# 230V2LED.net
KiCad netlist of a schematic drawn in EAGLE
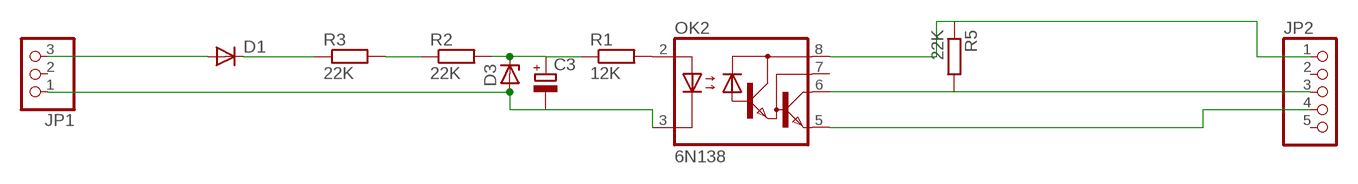
[diagram p0: schematic, sheet 1]

(export (version "E")
  (design (tool "Eeschema 10.0.6"))
  (components
    (comp (ref "C3")
      (value "CPOL-EUE2,5-6E")
      (footprint "eagle-import:E2,5-6E")
      (libsource (lib "eagle-import") (part "CPOL-EUE2,5-6E"))
    )
    (comp (ref "D1")
      (value "DIODE-D-2.5")
      (footprint "eagle-import:D-2.5")
      (libsource (lib "eagle-import") (part "DIODE-D-2.5"))
    )
    (comp (ref "D3")
      (value "ZENER-DIODEZD-2.5")
      (footprint "eagle-import:ZDIO-2.5")
      (libsource (lib "eagle-import") (part "ZENER-DIODEZD-2.5"))
    )
    (comp (ref "JP1")
      (value "PINHD-1X3")
      (footprint "eagle-import:1X03")
      (libsource (lib "eagle-import") (part "PINHD-1X3"))
    )
    (comp (ref "JP2")
      (value "PINHD-1X5")
      (footprint "eagle-import:1X05")
      (libsource (lib "eagle-import") (part "PINHD-1X5"))
    )
    (comp (ref "OK2")
      (value "6N138")
      (footprint "eagle-import:DIL08")
      (fields (field (name "MF") "VISHAY/TELEFUNKEN"))
      (libsource (lib "eagle-import") (part "6N138"))
    )
    (comp (ref "R1")
      (value "12K")
      (footprint "eagle-import:0207_2V")
      (libsource (lib "eagle-import") (part "R-EU_0207/2V"))
    )
    (comp (ref "R2")
      (value "22K")
      (footprint "eagle-import:0207_2V")
      (libsource (lib "eagle-import") (part "R-EU_0207/2V"))
    )
    (comp (ref "R3")
      (value "22K")
      (footprint "eagle-import:0207_2V")
      (libsource (lib "eagle-import") (part "R-EU_0207/2V"))
    )
    (comp (ref "R5")
      (value "22K")
      (footprint "eagle-import:0207_2V")
      (libsource (lib "eagle-import") (part "R-EU_0207/2V"))
    )
  )
  (nets
    (net (code "1") (name "Net-(C3-Pad+)") (class "Default")
      (node (ref "C3") (pin "+") (pinfunction "+_+") (pintype "passive"))
      (node (ref "D3") (pin "C") (pinfunction "C_C") (pintype "passive"))
      (node (ref "R1") (pin "1") (pinfunction "1_1") (pintype "passive"))
      (node (ref "R2") (pin "2") (pinfunction "2_2") (pintype "passive"))
    )
    (net (code "2") (name "Net-(D1-PadA)") (class "Default")
      (node (ref "D1") (pin "A") (pinfunction "A_A") (pintype "passive"))
      (node (ref "JP1") (pin "3") (pinfunction "3_3") (pintype "passive"))
    )
    (net (code "3") (name "Net-(D1-PadC)") (class "Default")
      (node (ref "D1") (pin "C") (pinfunction "C_C") (pintype "passive"))
      (node (ref "R3") (pin "1") (pinfunction "1_1") (pintype "passive"))
    )
    (net (code "4") (name "Net-(OK2-A)") (class "Default")
      (node (ref "OK2") (pin "2") (pinfunction "A_2") (pintype "passive"))
      (node (ref "R1") (pin "2") (pinfunction "2_2") (pintype "passive"))
    )
    (net (code "5") (name "Net-(OK2-C)") (class "Default")
      (node (ref "C3") (pin "-") (pinfunction "-_-") (pintype "passive"))
      (node (ref "D3") (pin "A") (pinfunction "A_A") (pintype "passive"))
      (node (ref "JP1") (pin "1") (pinfunction "1_1") (pintype "passive"))
      (node (ref "OK2") (pin "3") (pinfunction "C_3") (pintype "passive"))
    )
    (net (code "6") (name "Net-(OK2-GND)") (class "Default")
      (node (ref "JP2") (pin "4") (pinfunction "4_4") (pintype "passive"))
      (node (ref "OK2") (pin "5") (pinfunction "GND_5") (pintype "passive"))
    )
    (net (code "7") (name "Net-(OK2-VCC)") (class "Default")
      (node (ref "JP2") (pin "1") (pinfunction "1_1") (pintype "passive"))
      (node (ref "OK2") (pin "8") (pinfunction "VCC_8") (pintype "passive"))
      (node (ref "R5") (pin "1") (pinfunction "1_1") (pintype "passive"))
    )
    (net (code "8") (name "Net-(OK2-VO)") (class "Default")
      (node (ref "JP2") (pin "3") (pinfunction "3_3") (pintype "passive"))
      (node (ref "OK2") (pin "6") (pinfunction "VO_6") (pintype "passive"))
      (node (ref "R5") (pin "2") (pinfunction "2_2") (pintype "passive"))
    )
    (net (code "9") (name "Net-(R2-Pad1)") (class "Default")
      (node (ref "R2") (pin "1") (pinfunction "1_1") (pintype "passive"))
      (node (ref "R3") (pin "2") (pinfunction "2_2") (pintype "passive"))
    )
    (net (code "10") (name "unconnected-(JP1-Pad2)") (class "Default")
      (node (ref "JP1") (pin "2") (pinfunction "2_2") (pintype "passive"))
    )
    (net (code "11") (name "unconnected-(JP2-Pad2)") (class "Default")
      (node (ref "JP2") (pin "2") (pinfunction "2_2") (pintype "passive"))
    )
    (net (code "12") (name "unconnected-(JP2-Pad5)") (class "Default")
      (node (ref "JP2") (pin "5") (pinfunction "5_5") (pintype "passive"))
    )
    (net (code "13") (name "unconnected-(OK2-VB-Pad7)") (class "Default")
      (node (ref "OK2") (pin "7") (pinfunction "VB_7") (pintype "passive"))
    )
  )
)
